# PX4FMUv2_3_SCH2.net
KiCad netlist of a schematic drawn in Altium Designer
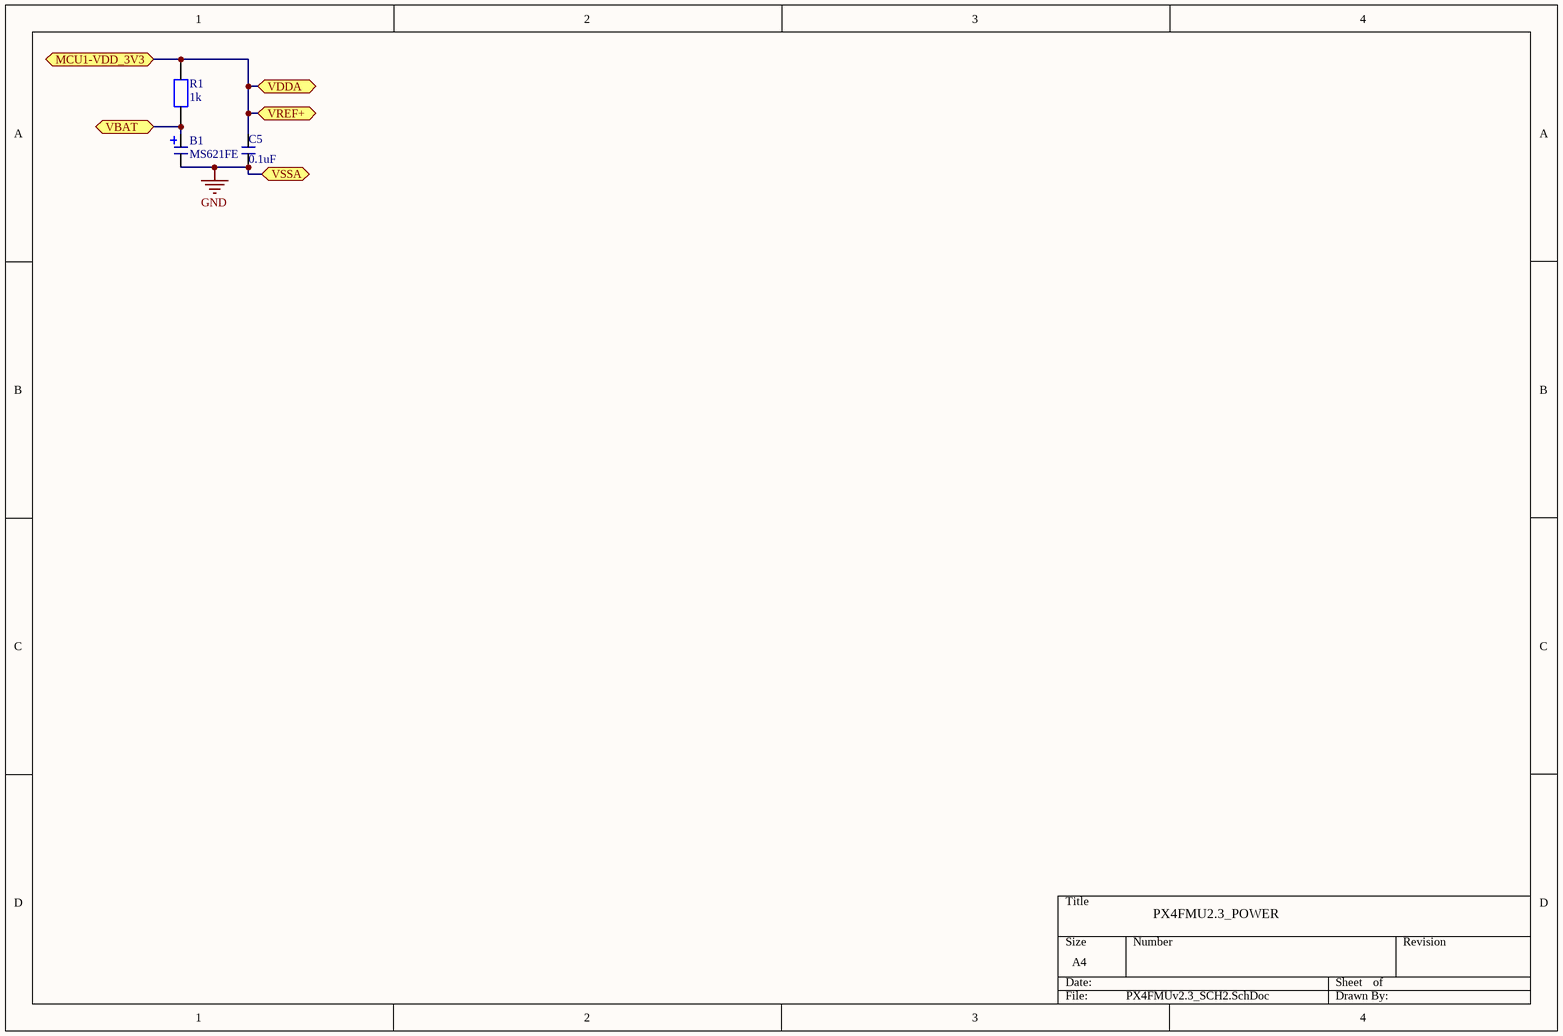
[diagram p0: PX4FMUv2.3_SCH2.SchDoc]

(export (version "E")
  (design (tool "Eeschema 10.0.6"))
  (components
    (comp (ref "B1") (value "MS621FE") (footprint "MS621FE") (libsource (lib "px4_SCHLIB") (part "MS621FE")))
    (comp (ref "C5") (value "0.1uF") (footprint "C 0402") (libsource (lib "px4_SCHLIB") (part "CAP_0402")))
    (comp (ref "R1") (value "1k") (footprint "0402R") (libsource (lib "px4_SCHLIB") (part "Res_0402")))
  )
  (nets
    (net (code "1") (name "/MCU1-VDD_3V3") (class "Default")
      (node (ref "C5") (pin "1") (pinfunction "1_1") (pintype "passive"))
      (node (ref "R1") (pin "2") (pinfunction "2_2") (pintype "passive"))
    )
    (net (code "2") (name "/VBAT") (class "Default")
      (node (ref "B1") (pin "1") (pinfunction "1_1") (pintype "passive"))
      (node (ref "R1") (pin "1") (pinfunction "1_1") (pintype "passive"))
    )
    (net (code "3") (name "GND") (class "Default")
      (node (ref "B1") (pin "2") (pinfunction "2_2") (pintype "passive"))
      (node (ref "C5") (pin "2") (pinfunction "2_2") (pintype "passive"))
    )
  )
)
